# rfboard.net
KiCad netlist of a schematic drawn in EAGLE
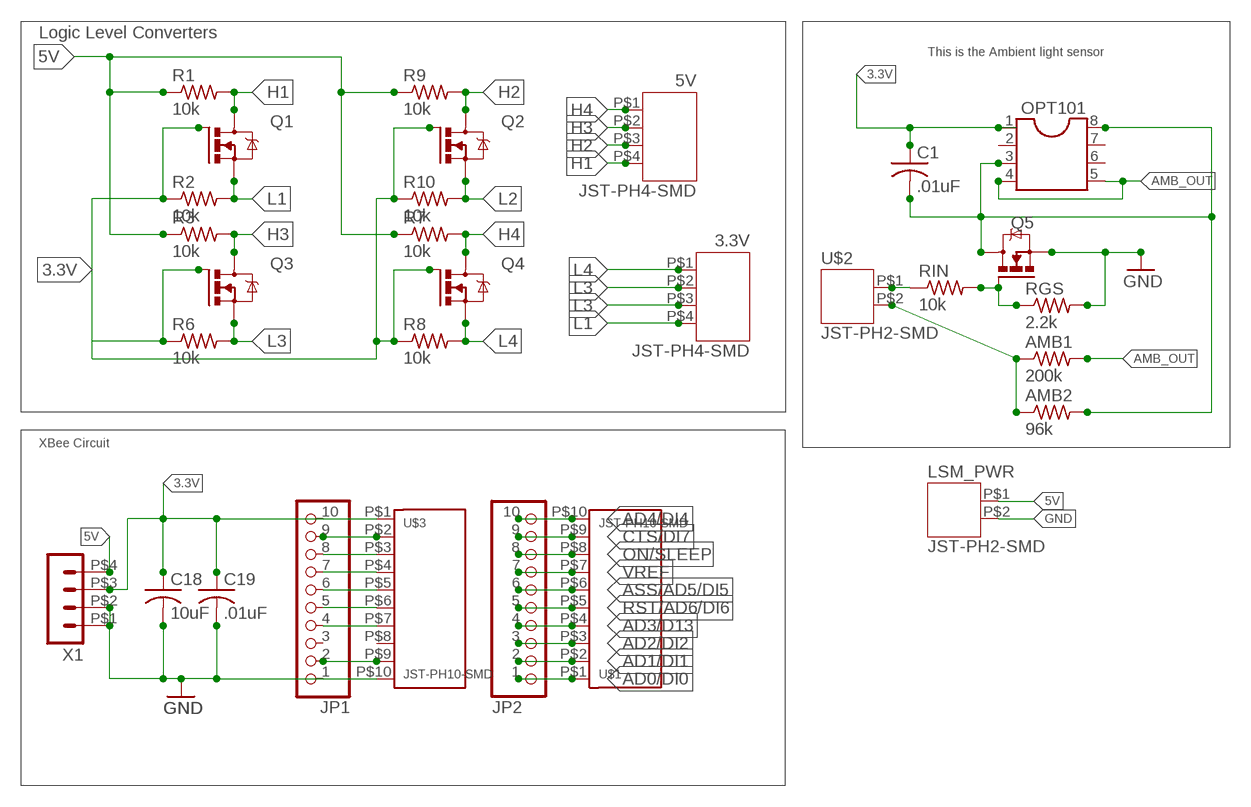
[diagram p0: schematic, sheet 1]

(export (version "E")
  (design (tool "Eeschema 10.0.6"))
  (components
    (comp (ref "3.3V")
      (value "JST-PH4-SMD")
      (footprint "eagle-import:JST-PH4-SMD")
      (libsource (lib "eagle-import") (part "JST-PH4-SMD"))
    )
    (comp (ref "5V")
      (value "JST-PH4-SMD")
      (footprint "eagle-import:JST-PH4-SMD")
      (libsource (lib "eagle-import") (part "JST-PH4-SMD"))
    )
    (comp (ref "AMB1")
      (value "200k")
      (footprint "eagle-import:R0805")
      (libsource (lib "eagle-import") (part "R-US_R0805"))
    )
    (comp (ref "AMB2")
      (value "96k")
      (footprint "eagle-import:R0805")
      (libsource (lib "eagle-import") (part "R-US_R0805"))
    )
    (comp (ref "C1")
      (value ".01uF")
      (footprint "eagle-import:C0805K")
      (libsource (lib "eagle-import") (part "C-USC0805K"))
    )
    (comp (ref "C18")
      (value "10uF")
      (footprint "eagle-import:C1206K")
      (libsource (lib "eagle-import") (part "C-USC1206K"))
    )
    (comp (ref "C19")
      (value ".01uF")
      (footprint "eagle-import:C0805K")
      (libsource (lib "eagle-import") (part "C-USC0805K"))
    )
    (comp (ref "JP1")
      (value "PINHD-1X10_2.00")
      (footprint "eagle-import:1X10M")
      (libsource (lib "eagle-import") (part "PINHD-1X10_2.00"))
    )
    (comp (ref "JP2")
      (value "PINHD-1X10_2.00")
      (footprint "eagle-import:1X10M")
      (libsource (lib "eagle-import") (part "PINHD-1X10_2.00"))
    )
    (comp (ref "LSM_PWR")
      (value "JST-PH2-SMD")
      (footprint "eagle-import:JST-PH2-SMD")
      (libsource (lib "eagle-import") (part "JST-PH2-SMD"))
    )
    (comp (ref "OPT101")
      (value "DIL8")
      (footprint "eagle-import:DIL08")
      (libsource (lib "eagle-import") (part "DIL8"))
    )
    (comp (ref "Q1")
      (value "IRLML5203")
      (footprint "eagle-import:MICRO3")
      (libsource (lib "eagle-import") (part "IRLML5203"))
    )
    (comp (ref "Q2")
      (value "IRLML5203")
      (footprint "eagle-import:MICRO3")
      (libsource (lib "eagle-import") (part "IRLML5203"))
    )
    (comp (ref "Q3")
      (value "IRLML5203")
      (footprint "eagle-import:MICRO3")
      (libsource (lib "eagle-import") (part "IRLML5203"))
    )
    (comp (ref "Q4")
      (value "IRLML5203")
      (footprint "eagle-import:MICRO3")
      (libsource (lib "eagle-import") (part "IRLML5203"))
    )
    (comp (ref "Q5")
      (value "IRLML5203")
      (footprint "eagle-import:MICRO3")
      (libsource (lib "eagle-import") (part "IRLML5203"))
    )
    (comp (ref "R1")
      (value "10k")
      (footprint "eagle-import:R0805")
      (libsource (lib "eagle-import") (part "R-US_R0805"))
    )
    (comp (ref "R2")
      (value "10k")
      (footprint "eagle-import:R0805")
      (libsource (lib "eagle-import") (part "R-US_R0805"))
    )
    (comp (ref "R3")
      (value "10k")
      (footprint "eagle-import:R0805")
      (libsource (lib "eagle-import") (part "R-US_R0805"))
    )
    (comp (ref "R6")
      (value "10k")
      (footprint "eagle-import:R0805")
      (libsource (lib "eagle-import") (part "R-US_R0805"))
    )
    (comp (ref "R7")
      (value "10k")
      (footprint "eagle-import:R0805")
      (libsource (lib "eagle-import") (part "R-US_R0805"))
    )
    (comp (ref "R8")
      (value "10k")
      (footprint "eagle-import:R0805")
      (libsource (lib "eagle-import") (part "R-US_R0805"))
    )
    (comp (ref "R9")
      (value "10k")
      (footprint "eagle-import:R0805")
      (libsource (lib "eagle-import") (part "R-US_R0805"))
    )
    (comp (ref "R10")
      (value "10k")
      (footprint "eagle-import:R0805")
      (libsource (lib "eagle-import") (part "R-US_R0805"))
    )
    (comp (ref "RGS")
      (value "2.2k")
      (footprint "eagle-import:R0805")
      (libsource (lib "eagle-import") (part "R-US_R0805"))
    )
    (comp (ref "RIN")
      (value "10k")
      (footprint "eagle-import:R0805")
      (libsource (lib "eagle-import") (part "R-US_R0805"))
    )
    (comp (ref "U$1")
      (value "JST-PH10-SMD")
      (footprint "eagle-import:JST-PH10-SMD")
      (libsource (lib "eagle-import") (part "JST-PH10-SMD"))
    )
    (comp (ref "U$2")
      (value "JST-PH2-SMD")
      (footprint "eagle-import:JST-PH2-SMD")
      (libsource (lib "eagle-import") (part "JST-PH2-SMD"))
    )
    (comp (ref "U$3")
      (value "JST-PH10-SMD")
      (footprint "eagle-import:JST-PH10-SMD")
      (libsource (lib "eagle-import") (part "JST-PH10-SMD"))
    )
    (comp (ref "X1")
      (value "HEADER_POS4_43045-0406")
      (footprint "eagle-import:43045-0406")
      (libsource (lib "eagle-import") (part "HEADER_POS4_?43045-0406"))
    )
  )
  (nets
    (net (code "1") (name "3.3V") (class "Default")
      (node (ref "C1") (pin "1") (pinfunction "1_1") (pintype "passive"))
      (node (ref "C18") (pin "1") (pinfunction "1_1") (pintype "passive"))
      (node (ref "C19") (pin "1") (pinfunction "1_1") (pintype "passive"))
      (node (ref "JP1") (pin "10") (pinfunction "10_10") (pintype "passive"))
      (node (ref "OPT101") (pin "1") (pinfunction "1_1") (pintype "passive"))
      (node (ref "Q1") (pin "1") (pinfunction "G_1") (pintype "passive"))
      (node (ref "Q2") (pin "1") (pinfunction "G_1") (pintype "passive"))
      (node (ref "Q3") (pin "1") (pinfunction "G_1") (pintype "passive"))
      (node (ref "Q4") (pin "1") (pinfunction "G_1") (pintype "passive"))
      (node (ref "R10") (pin "1") (pinfunction "1_1") (pintype "passive"))
      (node (ref "R2") (pin "1") (pinfunction "1_1") (pintype "passive"))
      (node (ref "R6") (pin "1") (pinfunction "1_1") (pintype "passive"))
      (node (ref "R8") (pin "1") (pinfunction "1_1") (pintype "passive"))
      (node (ref "U$3") (pin "P$1") (pinfunction "P$1_P$1") (pintype "bidirectional"))
      (node (ref "X1") (pin "P$3") (pinfunction "3_P$3") (pintype "passive"))
    )
    (net (code "2") (name "5V") (class "Default")
      (node (ref "LSM_PWR") (pin "P$1") (pinfunction "1_P$1") (pintype "passive"))
      (node (ref "R1") (pin "1") (pinfunction "1_1") (pintype "passive"))
      (node (ref "R3") (pin "1") (pinfunction "1_1") (pintype "passive"))
      (node (ref "R7") (pin "1") (pinfunction "1_1") (pintype "passive"))
      (node (ref "R9") (pin "1") (pinfunction "1_1") (pintype "passive"))
      (node (ref "X1") (pin "P$4") (pinfunction "4_P$4") (pintype "passive"))
    )
    (net (code "3") (name "AD0{slash}DI0") (class "Default")
      (node (ref "JP2") (pin "1") (pinfunction "1_1") (pintype "passive"))
      (node (ref "U$1") (pin "P$1") (pinfunction "P$1_P$1") (pintype "bidirectional"))
    )
    (net (code "4") (name "AD1{slash}DI1") (class "Default")
      (node (ref "JP2") (pin "2") (pinfunction "2_2") (pintype "passive"))
      (node (ref "U$1") (pin "P$2") (pinfunction "P$2_P$2") (pintype "bidirectional"))
    )
    (net (code "5") (name "AD2{slash}DI2") (class "Default")
      (node (ref "JP2") (pin "3") (pinfunction "3_3") (pintype "passive"))
      (node (ref "U$1") (pin "P$3") (pinfunction "P$3_P$3") (pintype "bidirectional"))
    )
    (net (code "6") (name "AD3{slash}D13") (class "Default")
      (node (ref "JP2") (pin "4") (pinfunction "4_4") (pintype "passive"))
      (node (ref "U$1") (pin "P$4") (pinfunction "P$4_P$4") (pintype "bidirectional"))
    )
    (net (code "7") (name "AD4{slash}DI4") (class "Default")
      (node (ref "JP2") (pin "10") (pinfunction "10_10") (pintype "passive"))
      (node (ref "U$1") (pin "P$10") (pinfunction "P$10_P$10") (pintype "bidirectional"))
    )
    (net (code "8") (name "AMB_OUT") (class "Default")
      (node (ref "AMB1") (pin "2") (pinfunction "2_2") (pintype "passive"))
      (node (ref "OPT101") (pin "4") (pinfunction "4_4") (pintype "passive"))
      (node (ref "OPT101") (pin "5") (pinfunction "5_5") (pintype "passive"))
    )
    (net (code "9") (name "ASS{slash}AD5{slash}DI5") (class "Default")
      (node (ref "JP2") (pin "6") (pinfunction "6_6") (pintype "passive"))
      (node (ref "U$1") (pin "P$6") (pinfunction "P$6_P$6") (pintype "bidirectional"))
    )
    (net (code "10") (name "CTS{slash}DI7") (class "Default")
      (node (ref "JP2") (pin "9") (pinfunction "9_9") (pintype "passive"))
      (node (ref "U$1") (pin "P$9") (pinfunction "P$9_P$9") (pintype "bidirectional"))
    )
    (net (code "11") (name "GND") (class "Default")
      (node (ref "C18") (pin "2") (pinfunction "2_2") (pintype "passive"))
      (node (ref "C19") (pin "2") (pinfunction "2_2") (pintype "passive"))
      (node (ref "JP1") (pin "1") (pinfunction "1_1") (pintype "passive"))
      (node (ref "LSM_PWR") (pin "P$2") (pinfunction "2_P$2") (pintype "passive"))
      (node (ref "Q5") (pin "3") (pinfunction "S_3") (pintype "passive"))
      (node (ref "RGS") (pin "2") (pinfunction "2_2") (pintype "passive"))
      (node (ref "U$3") (pin "P$10") (pinfunction "P$10_P$10") (pintype "bidirectional"))
      (node (ref "X1") (pin "P$1") (pinfunction "1_P$1") (pintype "passive"))
      (node (ref "X1") (pin "P$2") (pinfunction "2_P$2") (pintype "passive"))
    )
    (net (code "12") (name "H1") (class "Default")
      (node (ref "5V") (pin "P$4") (pinfunction "4_P$4") (pintype "passive"))
      (node (ref "Q1") (pin "2") (pinfunction "D_2") (pintype "passive"))
      (node (ref "R1") (pin "2") (pinfunction "2_2") (pintype "passive"))
    )
    (net (code "13") (name "H2") (class "Default")
      (node (ref "5V") (pin "P$3") (pinfunction "3_P$3") (pintype "passive"))
      (node (ref "Q2") (pin "2") (pinfunction "D_2") (pintype "passive"))
      (node (ref "R9") (pin "2") (pinfunction "2_2") (pintype "passive"))
    )
    (net (code "14") (name "H3") (class "Default")
      (node (ref "5V") (pin "P$2") (pinfunction "2_P$2") (pintype "passive"))
      (node (ref "Q3") (pin "2") (pinfunction "D_2") (pintype "passive"))
      (node (ref "R3") (pin "2") (pinfunction "2_2") (pintype "passive"))
    )
    (net (code "15") (name "H4") (class "Default")
      (node (ref "5V") (pin "P$1") (pinfunction "1_P$1") (pintype "passive"))
      (node (ref "Q4") (pin "2") (pinfunction "D_2") (pintype "passive"))
      (node (ref "R7") (pin "2") (pinfunction "2_2") (pintype "passive"))
    )
    (net (code "16") (name "L1") (class "Default")
      (node (ref "3.3V") (pin "P$4") (pinfunction "4_P$4") (pintype "passive"))
      (node (ref "Q1") (pin "3") (pinfunction "S_3") (pintype "passive"))
      (node (ref "R2") (pin "2") (pinfunction "2_2") (pintype "passive"))
    )
    (net (code "17") (name "L2") (class "Default")
      (node (ref "3.3V") (pin "P$3") (pinfunction "3_P$3") (pintype "passive"))
      (node (ref "Q2") (pin "3") (pinfunction "S_3") (pintype "passive"))
      (node (ref "R10") (pin "2") (pinfunction "2_2") (pintype "passive"))
    )
    (net (code "18") (name "L3") (class "Default")
      (node (ref "3.3V") (pin "P$2") (pinfunction "2_P$2") (pintype "passive"))
      (node (ref "Q3") (pin "3") (pinfunction "S_3") (pintype "passive"))
      (node (ref "R6") (pin "2") (pinfunction "2_2") (pintype "passive"))
    )
    (net (code "19") (name "L4") (class "Default")
      (node (ref "3.3V") (pin "P$1") (pinfunction "1_P$1") (pintype "passive"))
      (node (ref "Q4") (pin "3") (pinfunction "S_3") (pintype "passive"))
      (node (ref "R8") (pin "2") (pinfunction "2_2") (pintype "passive"))
    )
    (net (code "20") (name "Net-(JP1-Pad2)") (class "Default")
      (node (ref "JP1") (pin "2") (pinfunction "2_2") (pintype "passive"))
      (node (ref "U$3") (pin "P$9") (pinfunction "P$9_P$9") (pintype "bidirectional"))
    )
    (net (code "21") (name "Net-(JP1-Pad4)") (class "Default")
      (node (ref "JP1") (pin "4") (pinfunction "4_4") (pintype "passive"))
      (node (ref "U$3") (pin "P$7") (pinfunction "P$7_P$7") (pintype "bidirectional"))
    )
    (net (code "22") (name "Net-(JP1-Pad5)") (class "Default")
      (node (ref "JP1") (pin "5") (pinfunction "5_5") (pintype "passive"))
      (node (ref "U$3") (pin "P$6") (pinfunction "P$6_P$6") (pintype "bidirectional"))
    )
    (net (code "23") (name "Net-(JP1-Pad6)") (class "Default")
      (node (ref "JP1") (pin "6") (pinfunction "6_6") (pintype "passive"))
      (node (ref "U$3") (pin "P$5") (pinfunction "P$5_P$5") (pintype "bidirectional"))
    )
    (net (code "24") (name "Net-(JP1-Pad7)") (class "Default")
      (node (ref "JP1") (pin "7") (pinfunction "7_7") (pintype "passive"))
      (node (ref "U$3") (pin "P$4") (pinfunction "P$4_P$4") (pintype "bidirectional"))
    )
    (net (code "25") (name "Net-(JP1-Pad8)") (class "Default")
      (node (ref "JP1") (pin "8") (pinfunction "8_8") (pintype "passive"))
      (node (ref "U$3") (pin "P$3") (pinfunction "P$3_P$3") (pintype "bidirectional"))
    )
    (net (code "26") (name "Net-(JP1-Pad9)") (class "Default")
      (node (ref "JP1") (pin "9") (pinfunction "9_9") (pintype "passive"))
      (node (ref "U$3") (pin "P$2") (pinfunction "P$2_P$2") (pintype "bidirectional"))
    )
    (net (code "27") (name "Net-(Q5-D)") (class "Default")
      (node (ref "AMB2") (pin "2") (pinfunction "2_2") (pintype "passive"))
      (node (ref "C1") (pin "2") (pinfunction "2_2") (pintype "passive"))
      (node (ref "OPT101") (pin "3") (pinfunction "3_3") (pintype "passive"))
      (node (ref "OPT101") (pin "8") (pinfunction "8_8") (pintype "passive"))
      (node (ref "Q5") (pin "2") (pinfunction "D_2") (pintype "passive"))
    )
    (net (code "28") (name "Net-(Q5-G)") (class "Default")
      (node (ref "Q5") (pin "1") (pinfunction "G_1") (pintype "passive"))
      (node (ref "RGS") (pin "1") (pinfunction "1_1") (pintype "passive"))
      (node (ref "RIN") (pin "2") (pinfunction "2_2") (pintype "passive"))
    )
    (net (code "29") (name "Net-(U$2-1)") (class "Default")
      (node (ref "RIN") (pin "1") (pinfunction "1_1") (pintype "passive"))
      (node (ref "U$2") (pin "P$1") (pinfunction "1_P$1") (pintype "passive"))
    )
    (net (code "30") (name "Net-(U$2-2)") (class "Default")
      (node (ref "AMB1") (pin "1") (pinfunction "1_1") (pintype "passive"))
      (node (ref "AMB2") (pin "1") (pinfunction "1_1") (pintype "passive"))
      (node (ref "U$2") (pin "P$2") (pinfunction "2_P$2") (pintype "passive"))
    )
    (net (code "31") (name "ON{slash}SLEEP") (class "Default")
      (node (ref "JP2") (pin "8") (pinfunction "8_8") (pintype "passive"))
      (node (ref "U$1") (pin "P$8") (pinfunction "P$8_P$8") (pintype "bidirectional"))
    )
    (net (code "32") (name "RST{slash}AD6{slash}DI6") (class "Default")
      (node (ref "JP2") (pin "5") (pinfunction "5_5") (pintype "passive"))
      (node (ref "U$1") (pin "P$5") (pinfunction "P$5_P$5") (pintype "bidirectional"))
    )
    (net (code "33") (name "VREF") (class "Default")
      (node (ref "JP2") (pin "7") (pinfunction "7_7") (pintype "passive"))
      (node (ref "U$1") (pin "P$7") (pinfunction "P$7_P$7") (pintype "bidirectional"))
    )
    (net (code "34") (name "unconnected-(JP1-Pad3)") (class "Default")
      (node (ref "JP1") (pin "3") (pinfunction "3_3") (pintype "passive"))
    )
    (net (code "35") (name "unconnected-(OPT101-Pad2)") (class "Default")
      (node (ref "OPT101") (pin "2") (pinfunction "2_2") (pintype "passive"))
    )
    (net (code "36") (name "unconnected-(OPT101-Pad6)") (class "Default")
      (node (ref "OPT101") (pin "6") (pinfunction "6_6") (pintype "passive"))
    )
    (net (code "37") (name "unconnected-(OPT101-Pad7)") (class "Default")
      (node (ref "OPT101") (pin "7") (pinfunction "7_7") (pintype "passive"))
    )
    (net (code "38") (name "unconnected-(U$3-PadP$8)") (class "Default")
      (node (ref "U$3") (pin "P$8") (pinfunction "P$8_P$8") (pintype "bidirectional"))
    )
  )
)
